# DC-DC_Buck_Converter_Rev1.net
KiCad netlist of a schematic drawn in EAGLE
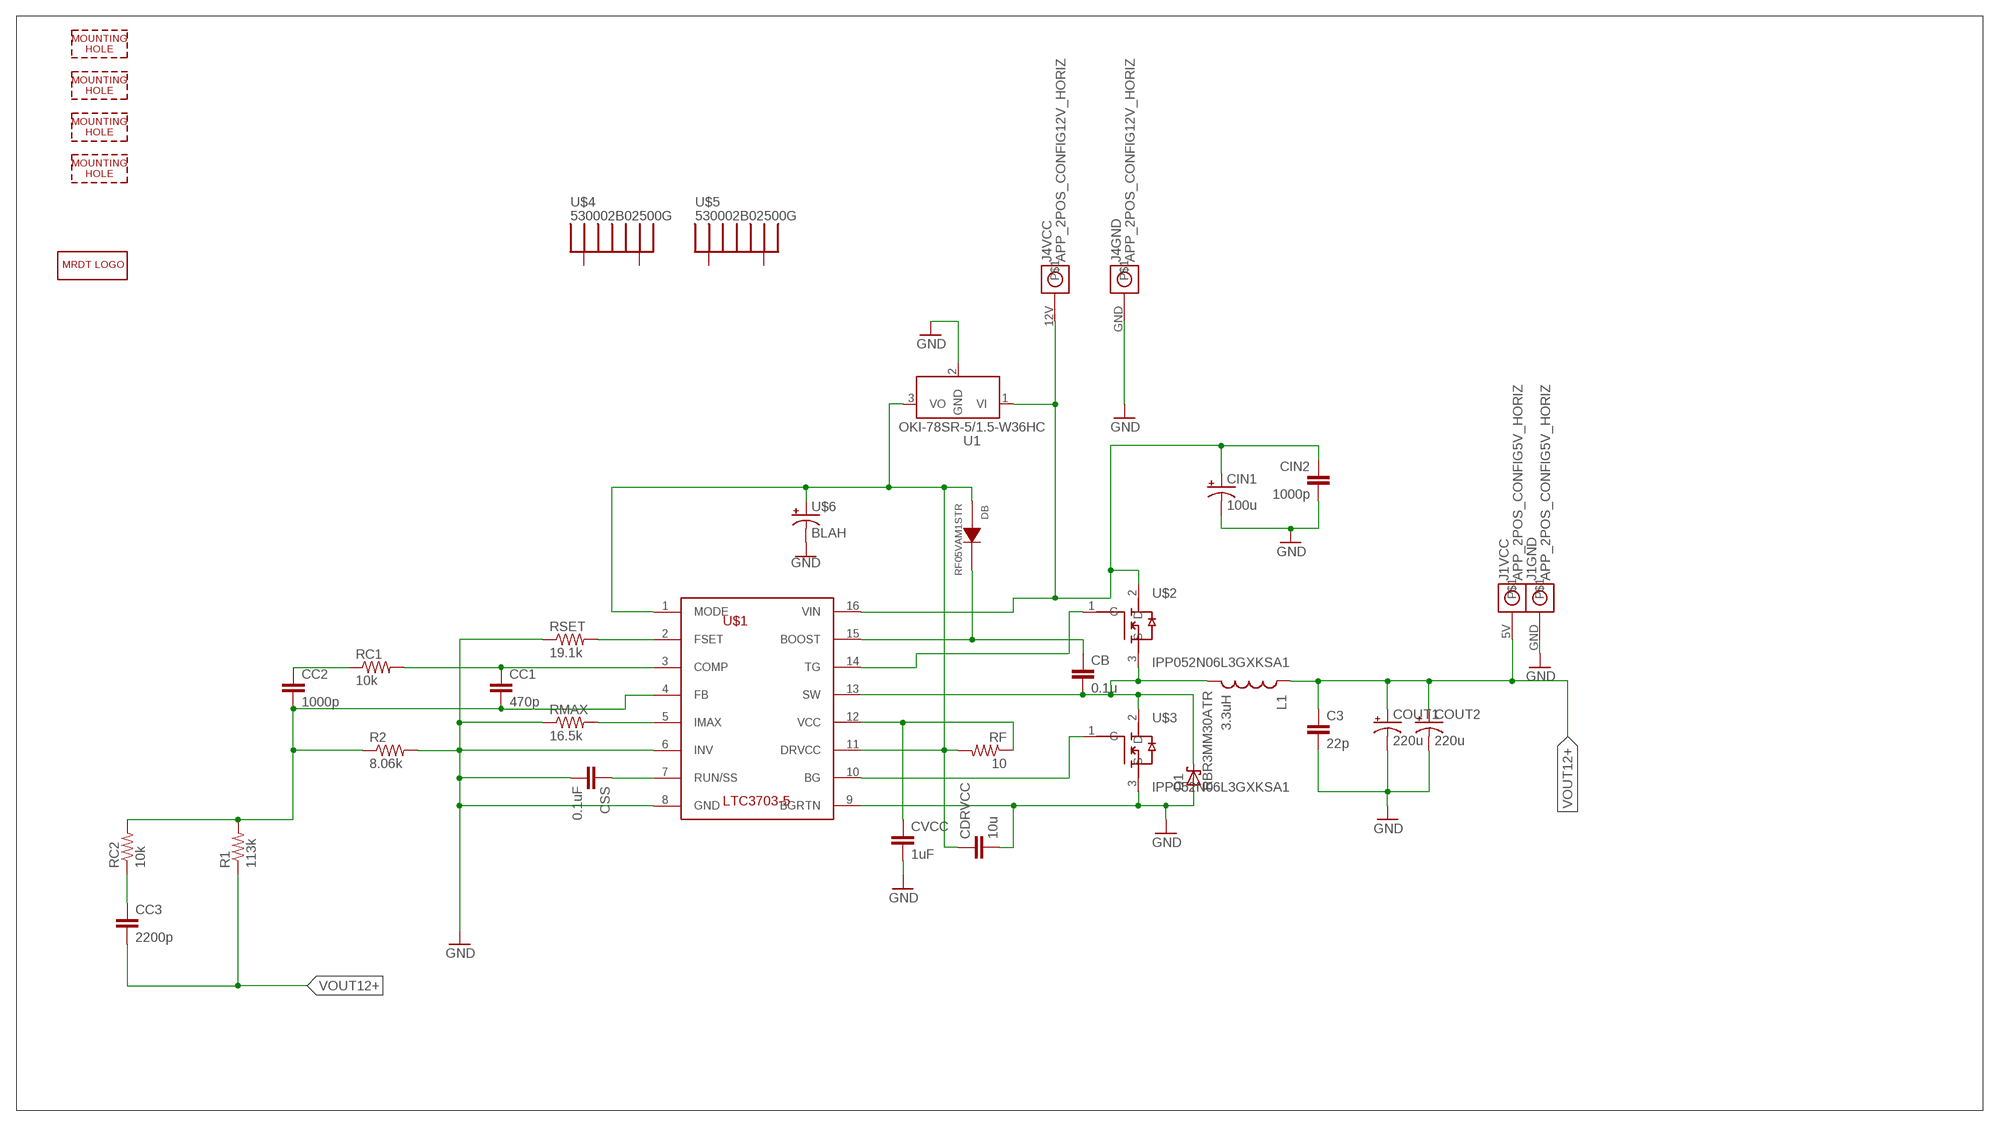
[diagram p0: schematic, sheet 1]

(export (version "E")
  (design (tool "Eeschema 10.0.6"))
  (components
    (comp (ref "C3")
      (value "22p")
      (footprint "eagle-import:0603-CAP")
      (libsource (lib "eagle-import") (part "CAP0603-CAP"))
    )
    (comp (ref "CB")
      (value "0.1u")
      (footprint "eagle-import:0603-CAP")
      (libsource (lib "eagle-import") (part "CAP0603-CAP"))
    )
    (comp (ref "CC1")
      (value "470p")
      (footprint "eagle-import:0603-CAP")
      (libsource (lib "eagle-import") (part "CAP0603-CAP"))
    )
    (comp (ref "CC2")
      (value "1000p")
      (footprint "eagle-import:0603-CAP")
      (libsource (lib "eagle-import") (part "CAP0603-CAP"))
    )
    (comp (ref "CC3")
      (value "2200p")
      (footprint "eagle-import:0603-CAP")
      (libsource (lib "eagle-import") (part "CAP0603-CAP"))
    )
    (comp (ref "CDRVCC")
      (value "10u")
      (footprint "eagle-import:0603-CAP")
      (libsource (lib "eagle-import") (part "CAP0603-CAP"))
    )
    (comp (ref "CIN1")
      (value "100u")
      (footprint "eagle-import:CAP_POL_220UF")
      (libsource (lib "eagle-import") (part "B41858C9107M000"))
    )
    (comp (ref "CIN2")
      (value "1000p")
      (footprint "eagle-import:0603-CAP")
      (libsource (lib "eagle-import") (part "CAP0603-CAP"))
    )
    (comp (ref "COUT1")
      (value "220u")
      (footprint "eagle-import:CAP_POL_220UF")
      (libsource (lib "eagle-import") (part "EGPD101ELL221MK25H"))
    )
    (comp (ref "COUT2")
      (value "220u")
      (footprint "eagle-import:CAP_POL_220UF")
      (libsource (lib "eagle-import") (part "EGPD101ELL221MK25H"))
    )
    (comp (ref "CSS")
      (value "0.1uF")
      (footprint "eagle-import:0603-CAP")
      (libsource (lib "eagle-import") (part "CAP0603-CAP"))
    )
    (comp (ref "CVCC")
      (value "1uF")
      (footprint "eagle-import:0603-CAP")
      (libsource (lib "eagle-import") (part "CAP0603-CAP"))
    )
    (comp (ref "D1")
      (value "RBR3MM30ATR")
      (footprint "eagle-import:DIODE_SCHOTTKY_30V_1A")
      (libsource (lib "eagle-import") (part "RBR3MM30ATR"))
    )
    (comp (ref "DB")
      (value "RF05VAM1STR")
      (footprint "eagle-import:DIODE_STANDARD_100V")
      (libsource (lib "eagle-import") (part "RF05VAM1STR"))
    )
    (comp (ref "H1")
      (value "MOUNTING_HOLE#8")
      (footprint "eagle-import:#8_SCREW")
      (libsource (lib "eagle-import") (part "MOUNTING_HOLE#8"))
    )
    (comp (ref "H2")
      (value "MOUNTING_HOLE#8")
      (footprint "eagle-import:#8_SCREW")
      (libsource (lib "eagle-import") (part "MOUNTING_HOLE#8"))
    )
    (comp (ref "H3")
      (value "MOUNTING_HOLE#8")
      (footprint "eagle-import:#8_SCREW")
      (libsource (lib "eagle-import") (part "MOUNTING_HOLE#8"))
    )
    (comp (ref "H4")
      (value "MOUNTING_HOLE#8")
      (footprint "eagle-import:#8_SCREW")
      (libsource (lib "eagle-import") (part "MOUNTING_HOLE#8"))
    )
    (comp (ref "J1")
      (value "APP_2POS_CONFIG5V_HORIZ")
      (footprint "eagle-import:APP45_5V_HORIZ_CONFIG")
      (libsource (lib "eagle-import") (part "APP_2POS_CONFIG5V_HORIZ"))
    )
    (comp (ref "J4")
      (value "APP_2POS_CONFIG12V_HORIZ")
      (footprint "eagle-import:APP45_12V_HORIZ_CONFIG")
      (libsource (lib "eagle-import") (part "APP_2POS_CONFIG12V_HORIZ"))
    )
    (comp (ref "L1")
      (value "3.3uH")
      (footprint "eagle-import:PLANAR_INDUCTOR_3.3UH")
      (libsource (lib "eagle-import") (part "PQ3218-3R3-70-T"))
    )
    (comp (ref "LOGO1")
      (value "MRDT_LOGO")
      (footprint "eagle-import:MRDT_LOGO")
      (libsource (lib "eagle-import") (part "MRDT_LOGO"))
    )
    (comp (ref "R1")
      (value "113k")
      (footprint "eagle-import:0603-RES")
      (libsource (lib "eagle-import") (part "RESISTOR0603-RES"))
    )
    (comp (ref "R2")
      (value "8.06k")
      (footprint "eagle-import:0603-RES")
      (libsource (lib "eagle-import") (part "RESISTOR0603-RES"))
    )
    (comp (ref "RC1")
      (value "10k")
      (footprint "eagle-import:0603-RES")
      (libsource (lib "eagle-import") (part "RESISTOR0603-RES"))
    )
    (comp (ref "RC2")
      (value "10k")
      (footprint "eagle-import:0603-RES")
      (libsource (lib "eagle-import") (part "RESISTOR0603-RES"))
    )
    (comp (ref "RF")
      (value "10")
      (footprint "eagle-import:0603-RES")
      (libsource (lib "eagle-import") (part "RESISTOR0603-RES"))
    )
    (comp (ref "RMAX")
      (value "16.5k")
      (footprint "eagle-import:0603-RES")
      (libsource (lib "eagle-import") (part "RESISTOR0603-RES"))
    )
    (comp (ref "RSET")
      (value "19.1k")
      (footprint "eagle-import:0603-RES")
      (libsource (lib "eagle-import") (part "RESISTOR0603-RES"))
    )
    (comp (ref "U$1")
      (value "LTC3703-5")
      (footprint "eagle-import:SSOP-16")
      (libsource (lib "eagle-import") (part "LTC3703-5"))
    )
    (comp (ref "U$2")
      (value "IPP052N06L3GXKSA1")
      (footprint "eagle-import:TO-220")
      (libsource (lib "eagle-import") (part "IPP052N06L3GXKSA1"))
    )
    (comp (ref "U$3")
      (value "IPP052N06L3GXKSA1")
      (footprint "eagle-import:TO-220")
      (libsource (lib "eagle-import") (part "IPP052N06L3GXKSA1"))
    )
    (comp (ref "U$4")
      (value "530002B02500G")
      (footprint "eagle-import:RADIAL_FIN_HEATSINK")
      (libsource (lib "eagle-import") (part "530002B02500G"))
    )
    (comp (ref "U$5")
      (value "530002B02500G")
      (footprint "eagle-import:RADIAL_FIN_HEATSINK")
      (libsource (lib "eagle-import") (part "530002B02500G"))
    )
    (comp (ref "U$6")
      (value "BLAH")
      (footprint "eagle-import:BLAH")
      (libsource (lib "eagle-import") (part "BLAH"))
    )
    (comp (ref "U1")
      (value "OKI-78SR-5/1.5-W36HC")
      (footprint "eagle-import:OKI-78SR_HORIZ")
      (libsource (lib "eagle-import") (part "OKI-78SR-/1.5-W36?CH5"))
    )
  )
  (nets
    (net (code "1") (name "GND") (class "Default")
      (node (ref "C3") (pin "2") (pinfunction "2_2") (pintype "passive"))
      (node (ref "CDRVCC") (pin "2") (pinfunction "2_2") (pintype "passive"))
      (node (ref "CIN1") (pin "GND") (pinfunction "-_GND") (pintype "passive"))
      (node (ref "CIN2") (pin "2") (pinfunction "2_2") (pintype "passive"))
      (node (ref "COUT1") (pin "GND") (pinfunction "-_GND") (pintype "passive"))
      (node (ref "COUT2") (pin "GND") (pinfunction "-_GND") (pintype "passive"))
      (node (ref "CSS") (pin "2") (pinfunction "2_2") (pintype "passive"))
      (node (ref "CVCC") (pin "2") (pinfunction "2_2") (pintype "passive"))
      (node (ref "D1") (pin "P$1") (pinfunction "A_P$1") (pintype "passive"))
      (node (ref "J1") (pin "GND") (pinfunction "P$1_GND") (pintype "bidirectional"))
      (node (ref "J4") (pin "GND") (pinfunction "P$1_GND") (pintype "bidirectional"))
      (node (ref "R2") (pin "2") (pinfunction "2_2") (pintype "passive"))
      (node (ref "RMAX") (pin "1") (pinfunction "1_1") (pintype "passive"))
      (node (ref "RSET") (pin "1") (pinfunction "1_1") (pintype "passive"))
      (node (ref "U$1") (pin "6") (pinfunction "INV_6") (pintype "bidirectional"))
      (node (ref "U$1") (pin "8") (pinfunction "GND_8") (pintype "bidirectional"))
      (node (ref "U$1") (pin "9") (pinfunction "BGRTN_9") (pintype "bidirectional"))
      (node (ref "U$3") (pin "3") (pinfunction "S_3") (pintype "bidirectional"))
      (node (ref "U$6") (pin "P$1") (pinfunction "-_P$1") (pintype "passive"))
      (node (ref "U1") (pin "2") (pinfunction "GND_2") (pintype "bidirectional"))
    )
    (net (code "2") (name "Net-(CC2-Pad1)") (class "Default")
      (node (ref "CC2") (pin "1") (pinfunction "1_1") (pintype "passive"))
      (node (ref "RC1") (pin "1") (pinfunction "1_1") (pintype "passive"))
    )
    (net (code "3") (name "Net-(CC3-Pad1)") (class "Default")
      (node (ref "CC3") (pin "1") (pinfunction "1_1") (pintype "passive"))
      (node (ref "RC2") (pin "1") (pinfunction "1_1") (pintype "passive"))
    )
    (net (code "4") (name "Net-(D1-C)") (class "Default")
      (node (ref "CB") (pin "2") (pinfunction "2_2") (pintype "passive"))
      (node (ref "D1") (pin "P$2") (pinfunction "C_P$2") (pintype "passive"))
      (node (ref "L1") (pin "P$2") (pinfunction "2_P$2") (pintype "passive"))
      (node (ref "U$1") (pin "13") (pinfunction "SW_13") (pintype "bidirectional"))
      (node (ref "U$2") (pin "3") (pinfunction "S_3") (pintype "bidirectional"))
      (node (ref "U$3") (pin "2") (pinfunction "D_2") (pintype "bidirectional"))
    )
    (net (code "5") (name "Net-(DB-A)") (class "Default")
      (node (ref "CDRVCC") (pin "1") (pinfunction "1_1") (pintype "passive"))
      (node (ref "DB") (pin "P$2") (pinfunction "A_P$2") (pintype "bidirectional"))
      (node (ref "RF") (pin "2") (pinfunction "2_2") (pintype "passive"))
      (node (ref "U$1") (pin "1") (pinfunction "MODE_1") (pintype "bidirectional"))
      (node (ref "U$1") (pin "11") (pinfunction "DRVCC_11") (pintype "bidirectional"))
      (node (ref "U$6") (pin "P$2") (pinfunction "+_P$2") (pintype "passive"))
      (node (ref "U1") (pin "3") (pinfunction "VO_3") (pintype "bidirectional"))
    )
    (net (code "6") (name "Net-(DB-K)") (class "Default")
      (node (ref "CB") (pin "1") (pinfunction "1_1") (pintype "passive"))
      (node (ref "DB") (pin "P$1") (pinfunction "K_P$1") (pintype "bidirectional"))
      (node (ref "U$1") (pin "15") (pinfunction "BOOST_15") (pintype "bidirectional"))
    )
    (net (code "7") (name "Net-(J4B-P$1)") (class "Default")
      (node (ref "CIN1") (pin "+") (pinfunction "+_+") (pintype "passive"))
      (node (ref "CIN2") (pin "1") (pinfunction "1_1") (pintype "passive"))
      (node (ref "J4") (pin "12V") (pinfunction "P$1_12V") (pintype "bidirectional"))
      (node (ref "U$1") (pin "16") (pinfunction "VIN_16") (pintype "bidirectional"))
      (node (ref "U$2") (pin "2") (pinfunction "D_2") (pintype "bidirectional"))
      (node (ref "U1") (pin "1") (pinfunction "VI_1") (pintype "bidirectional"))
    )
    (net (code "8") (name "Net-(U$1-BG)") (class "Default")
      (node (ref "U$1") (pin "10") (pinfunction "BG_10") (pintype "bidirectional"))
      (node (ref "U$3") (pin "1") (pinfunction "G_1") (pintype "bidirectional"))
    )
    (net (code "9") (name "Net-(U$1-COMP)") (class "Default")
      (node (ref "CC1") (pin "1") (pinfunction "1_1") (pintype "passive"))
      (node (ref "RC1") (pin "2") (pinfunction "2_2") (pintype "passive"))
      (node (ref "U$1") (pin "3") (pinfunction "COMP_3") (pintype "bidirectional"))
    )
    (net (code "10") (name "Net-(U$1-FB)") (class "Default")
      (node (ref "CC1") (pin "2") (pinfunction "2_2") (pintype "passive"))
      (node (ref "CC2") (pin "2") (pinfunction "2_2") (pintype "passive"))
      (node (ref "R1") (pin "2") (pinfunction "2_2") (pintype "passive"))
      (node (ref "R2") (pin "1") (pinfunction "1_1") (pintype "passive"))
      (node (ref "RC2") (pin "2") (pinfunction "2_2") (pintype "passive"))
      (node (ref "U$1") (pin "4") (pinfunction "FB_4") (pintype "bidirectional"))
    )
    (net (code "11") (name "Net-(U$1-FSET)") (class "Default")
      (node (ref "RSET") (pin "2") (pinfunction "2_2") (pintype "passive"))
      (node (ref "U$1") (pin "2") (pinfunction "FSET_2") (pintype "bidirectional"))
    )
    (net (code "12") (name "Net-(U$1-IMAX)") (class "Default")
      (node (ref "RMAX") (pin "2") (pinfunction "2_2") (pintype "passive"))
      (node (ref "U$1") (pin "5") (pinfunction "IMAX_5") (pintype "bidirectional"))
    )
    (net (code "13") (name "Net-(U$1-RUN{slash}SS)") (class "Default")
      (node (ref "CSS") (pin "1") (pinfunction "1_1") (pintype "passive"))
      (node (ref "U$1") (pin "7") (pinfunction "RUN/SS_7") (pintype "bidirectional"))
    )
    (net (code "14") (name "Net-(U$1-TG)") (class "Default")
      (node (ref "U$1") (pin "14") (pinfunction "TG_14") (pintype "bidirectional"))
      (node (ref "U$2") (pin "1") (pinfunction "G_1") (pintype "bidirectional"))
    )
    (net (code "15") (name "Net-(U$1-VCC)") (class "Default")
      (node (ref "CVCC") (pin "1") (pinfunction "1_1") (pintype "passive"))
      (node (ref "RF") (pin "1") (pinfunction "1_1") (pintype "passive"))
      (node (ref "U$1") (pin "12") (pinfunction "VCC_12") (pintype "bidirectional"))
    )
    (net (code "16") (name "VOUT12+") (class "Default")
      (node (ref "C3") (pin "1") (pinfunction "1_1") (pintype "passive"))
      (node (ref "CC3") (pin "2") (pinfunction "2_2") (pintype "passive"))
      (node (ref "COUT1") (pin "+") (pinfunction "+_+") (pintype "passive"))
      (node (ref "COUT2") (pin "+") (pinfunction "+_+") (pintype "passive"))
      (node (ref "J1") (pin "5V") (pinfunction "P$1_5V") (pintype "bidirectional"))
      (node (ref "L1") (pin "P$1") (pinfunction "1_P$1") (pintype "passive"))
      (node (ref "R1") (pin "1") (pinfunction "1_1") (pintype "passive"))
    )
    (net (code "17") (name "unconnected-(U$4-PadP$1)") (class "Default")
      (node (ref "U$4") (pin "P$1") (pinfunction "P$1_P$1") (pintype "bidirectional"))
    )
    (net (code "18") (name "unconnected-(U$4-PadP$2)") (class "Default")
      (node (ref "U$4") (pin "P$2") (pinfunction "P$2_P$2") (pintype "bidirectional"))
    )
    (net (code "19") (name "unconnected-(U$5-PadP$1)") (class "Default")
      (node (ref "U$5") (pin "P$1") (pinfunction "P$1_P$1") (pintype "bidirectional"))
    )
    (net (code "20") (name "unconnected-(U$5-PadP$2)") (class "Default")
      (node (ref "U$5") (pin "P$2") (pinfunction "P$2_P$2") (pintype "bidirectional"))
    )
  )
)
